# Sheet2.net
KiCad netlist of a schematic drawn in Altium Designer
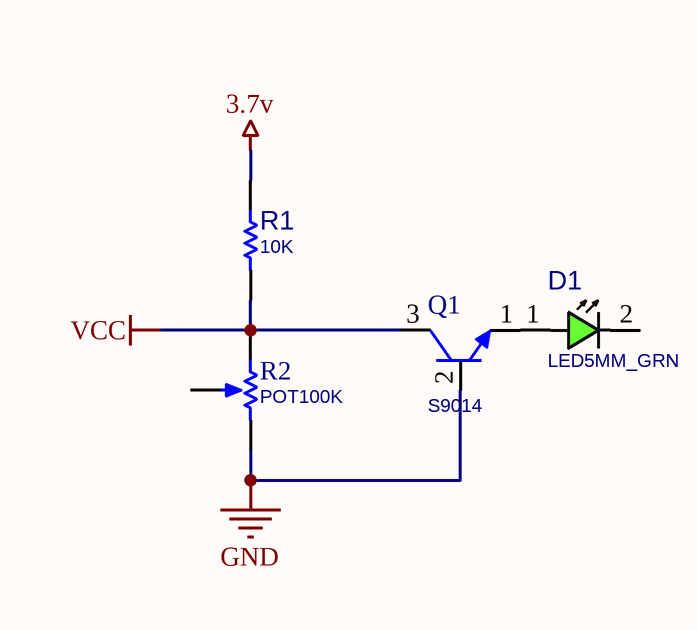
[diagram p0: Sheet2.SchDoc]

(export (version "E")
  (design (tool "Eeschema 10.0.6"))
  (components
    (comp (ref "D1")
      (value "LED5MM_GRN")
      (footprint "LED5MM_GRN")
      (description "LED, THD, 5MM, GREEN")
      (fields (field (name "MANF") "MANF") (field (name "MANF_P#") "MANF_PART#"))
      (libsource (lib "led(diode)") (part "LED_THD_5MM_GRN"))
    )
    (comp (ref "Q1")
      (value "S9014")
      (footprint "TO92_3")
      (description "BJT, NPN, 45v, 0.1A, THD, TO92")
      (libsource (lib "transistor_bjt") (part "NPN_S9014_TO92"))
    )
    (comp (ref "R1")
      (value "10K")
      (footprint "R025W_AX04")
      (description "RESISTOR, THD")
      (fields (field (name "MANF_P#") "RK73H1ETTP4701F") (field (name "MANF") "KOA SPEER"))
      (libsource (lib "passive_thd") (part "RES_THD"))
    )
    (comp (ref "R2")
      (value "POT100K")
      (footprint "POT_7X5")
      (description "RESISTOR, THD, Potentiometer")
      (libsource (lib "resistor_pot_trimmer") (part "RES_THD_POT_7X5"))
    )
  )
  (nets
    (net (code "1") (name "3.7v") (class "Default")
      (node (ref "R1") (pin "1") (pinfunction "1_1") (pintype "passive"))
    )
    (net (code "2") (name "GND") (class "Default")
      (node (ref "Q1") (pin "2") (pinfunction "B_2") (pintype "passive"))
      (node (ref "R2") (pin "3") (pinfunction "BOT_3") (pintype "passive"))
    )
    (net (code "3") (name "Net-(D1-ANODE)") (class "Default")
      (node (ref "D1") (pin "1") (pinfunction "ANODE_1") (pintype "passive"))
      (node (ref "Q1") (pin "1") (pinfunction "E_1") (pintype "passive"))
    )
    (net (code "4") (name "VCC") (class "Default")
      (node (ref "Q1") (pin "3") (pinfunction "C_3") (pintype "passive"))
      (node (ref "R1") (pin "2") (pinfunction "2_2") (pintype "passive"))
      (node (ref "R2") (pin "1") (pinfunction "TOP_1") (pintype "passive"))
    )
    (net (code "5") (name "unconnected-(D1-CATHODE-Pad2)") (class "Default")
      (node (ref "D1") (pin "2") (pinfunction "CATHODE_2") (pintype "passive"))
    )
    (net (code "6") (name "unconnected-(R2-TAP-Pad2)") (class "Default")
      (node (ref "R2") (pin "2") (pinfunction "TAP_2") (pintype "passive"))
    )
  )
)
